# flatsat-breakout-main.net
KiCad netlist of a schematic drawn in EAGLE
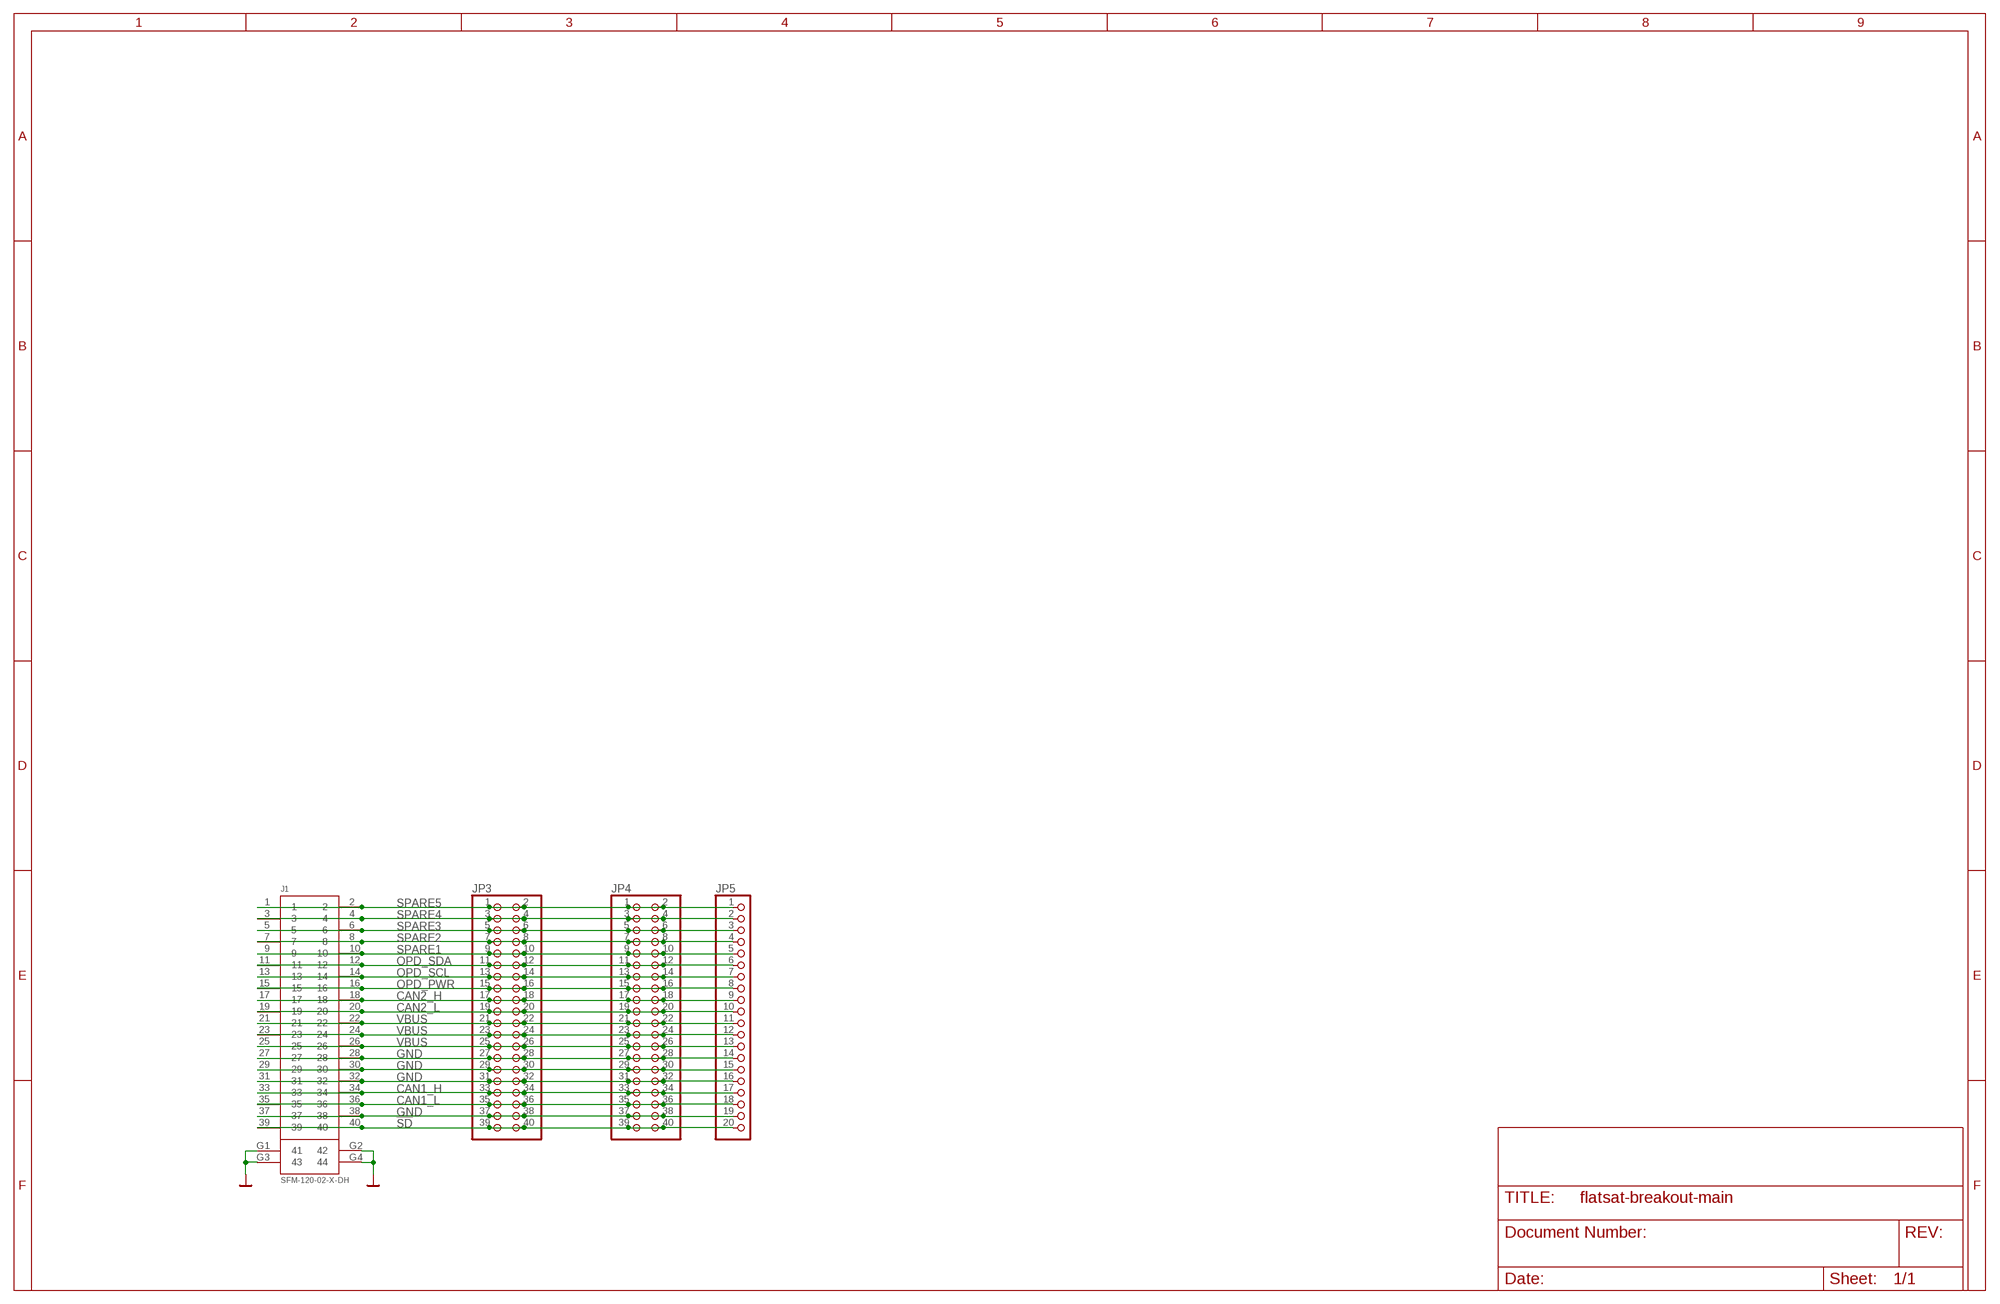
[diagram p0: schematic, sheet 1]

(export (version "E")
  (design (tool "Eeschema 10.0.6"))
  (components
    (comp (ref "J1")
      (value "SFM-120-02-X-DH")
      (footprint "eagle-import:SFM-120-02-X-DH")
      (libsource (lib "eagle-import") (part "SFM-120-02-X-DH"))
    )
    (comp (ref "JP3")
      (value "PINHD-2X20")
      (footprint "eagle-import:2X20")
      (libsource (lib "eagle-import") (part "PINHD-2X20"))
    )
    (comp (ref "JP4")
      (value "PINHD-2X20")
      (footprint "eagle-import:2X20")
      (libsource (lib "eagle-import") (part "PINHD-2X20"))
    )
    (comp (ref "JP5")
      (value "PINHD-1X20")
      (footprint "eagle-import:1X20")
      (libsource (lib "eagle-import") (part "PINHD-1X20"))
    )
  )
  (nets
    (net (code "1") (name "/CAN1_H") (class "Default")
      (node (ref "J1") (pin "33") (pinfunction "33_33") (pintype "bidirectional"))
      (node (ref "J1") (pin "34") (pinfunction "34_34") (pintype "bidirectional"))
      (node (ref "JP3") (pin "33") (pinfunction "33_33") (pintype "passive"))
      (node (ref "JP3") (pin "34") (pinfunction "34_34") (pintype "passive"))
      (node (ref "JP4") (pin "33") (pinfunction "33_33") (pintype "passive"))
      (node (ref "JP4") (pin "34") (pinfunction "34_34") (pintype "passive"))
      (node (ref "JP5") (pin "17") (pinfunction "17_17") (pintype "passive"))
    )
    (net (code "2") (name "/CAN1_L") (class "Default")
      (node (ref "J1") (pin "35") (pinfunction "35_35") (pintype "bidirectional"))
      (node (ref "J1") (pin "36") (pinfunction "36_36") (pintype "bidirectional"))
      (node (ref "JP3") (pin "35") (pinfunction "35_35") (pintype "passive"))
      (node (ref "JP3") (pin "36") (pinfunction "36_36") (pintype "passive"))
      (node (ref "JP4") (pin "35") (pinfunction "35_35") (pintype "passive"))
      (node (ref "JP4") (pin "36") (pinfunction "36_36") (pintype "passive"))
      (node (ref "JP5") (pin "18") (pinfunction "18_18") (pintype "passive"))
    )
    (net (code "3") (name "/CAN2_H") (class "Default")
      (node (ref "J1") (pin "17") (pinfunction "17_17") (pintype "bidirectional"))
      (node (ref "J1") (pin "18") (pinfunction "18_18") (pintype "bidirectional"))
      (node (ref "JP3") (pin "17") (pinfunction "17_17") (pintype "passive"))
      (node (ref "JP3") (pin "18") (pinfunction "18_18") (pintype "passive"))
      (node (ref "JP4") (pin "17") (pinfunction "17_17") (pintype "passive"))
      (node (ref "JP4") (pin "18") (pinfunction "18_18") (pintype "passive"))
      (node (ref "JP5") (pin "9") (pinfunction "9_9") (pintype "passive"))
    )
    (net (code "4") (name "/CAN2_L") (class "Default")
      (node (ref "J1") (pin "19") (pinfunction "19_19") (pintype "bidirectional"))
      (node (ref "J1") (pin "20") (pinfunction "20_20") (pintype "bidirectional"))
      (node (ref "JP3") (pin "19") (pinfunction "19_19") (pintype "passive"))
      (node (ref "JP3") (pin "20") (pinfunction "20_20") (pintype "passive"))
      (node (ref "JP4") (pin "19") (pinfunction "19_19") (pintype "passive"))
      (node (ref "JP4") (pin "20") (pinfunction "20_20") (pintype "passive"))
      (node (ref "JP5") (pin "10") (pinfunction "10_10") (pintype "passive"))
    )
    (net (code "5") (name "/OPD_PWR") (class "Default")
      (node (ref "J1") (pin "15") (pinfunction "15_15") (pintype "bidirectional"))
      (node (ref "J1") (pin "16") (pinfunction "16_16") (pintype "bidirectional"))
      (node (ref "JP3") (pin "15") (pinfunction "15_15") (pintype "passive"))
      (node (ref "JP3") (pin "16") (pinfunction "16_16") (pintype "passive"))
      (node (ref "JP4") (pin "15") (pinfunction "15_15") (pintype "passive"))
      (node (ref "JP4") (pin "16") (pinfunction "16_16") (pintype "passive"))
      (node (ref "JP5") (pin "8") (pinfunction "8_8") (pintype "passive"))
    )
    (net (code "6") (name "/OPD_SCL") (class "Default")
      (node (ref "J1") (pin "13") (pinfunction "13_13") (pintype "bidirectional"))
      (node (ref "J1") (pin "14") (pinfunction "14_14") (pintype "bidirectional"))
      (node (ref "JP3") (pin "13") (pinfunction "13_13") (pintype "passive"))
      (node (ref "JP3") (pin "14") (pinfunction "14_14") (pintype "passive"))
      (node (ref "JP4") (pin "13") (pinfunction "13_13") (pintype "passive"))
      (node (ref "JP4") (pin "14") (pinfunction "14_14") (pintype "passive"))
      (node (ref "JP5") (pin "7") (pinfunction "7_7") (pintype "passive"))
    )
    (net (code "7") (name "/OPD_SDA") (class "Default")
      (node (ref "J1") (pin "11") (pinfunction "11_11") (pintype "bidirectional"))
      (node (ref "J1") (pin "12") (pinfunction "12_12") (pintype "bidirectional"))
      (node (ref "JP3") (pin "11") (pinfunction "11_11") (pintype "passive"))
      (node (ref "JP3") (pin "12") (pinfunction "12_12") (pintype "passive"))
      (node (ref "JP4") (pin "11") (pinfunction "11_11") (pintype "passive"))
      (node (ref "JP4") (pin "12") (pinfunction "12_12") (pintype "passive"))
      (node (ref "JP5") (pin "6") (pinfunction "6_6") (pintype "passive"))
    )
    (net (code "8") (name "/SPARE1") (class "Default")
      (node (ref "J1") (pin "10") (pinfunction "10_10") (pintype "bidirectional"))
      (node (ref "J1") (pin "9") (pinfunction "9_9") (pintype "bidirectional"))
      (node (ref "JP3") (pin "10") (pinfunction "10_10") (pintype "passive"))
      (node (ref "JP3") (pin "9") (pinfunction "9_9") (pintype "passive"))
      (node (ref "JP4") (pin "10") (pinfunction "10_10") (pintype "passive"))
      (node (ref "JP4") (pin "9") (pinfunction "9_9") (pintype "passive"))
      (node (ref "JP5") (pin "5") (pinfunction "5_5") (pintype "passive"))
    )
    (net (code "9") (name "/SPARE2") (class "Default")
      (node (ref "J1") (pin "7") (pinfunction "7_7") (pintype "bidirectional"))
      (node (ref "J1") (pin "8") (pinfunction "8_8") (pintype "bidirectional"))
      (node (ref "JP3") (pin "7") (pinfunction "7_7") (pintype "passive"))
      (node (ref "JP3") (pin "8") (pinfunction "8_8") (pintype "passive"))
      (node (ref "JP4") (pin "7") (pinfunction "7_7") (pintype "passive"))
      (node (ref "JP4") (pin "8") (pinfunction "8_8") (pintype "passive"))
      (node (ref "JP5") (pin "4") (pinfunction "4_4") (pintype "passive"))
    )
    (net (code "10") (name "/SPARE3") (class "Default")
      (node (ref "J1") (pin "5") (pinfunction "5_5") (pintype "bidirectional"))
      (node (ref "J1") (pin "6") (pinfunction "6_6") (pintype "bidirectional"))
      (node (ref "JP3") (pin "5") (pinfunction "5_5") (pintype "passive"))
      (node (ref "JP3") (pin "6") (pinfunction "6_6") (pintype "passive"))
      (node (ref "JP4") (pin "5") (pinfunction "5_5") (pintype "passive"))
      (node (ref "JP4") (pin "6") (pinfunction "6_6") (pintype "passive"))
      (node (ref "JP5") (pin "3") (pinfunction "3_3") (pintype "passive"))
    )
    (net (code "11") (name "/SPARE4") (class "Default")
      (node (ref "J1") (pin "3") (pinfunction "3_3") (pintype "bidirectional"))
      (node (ref "J1") (pin "4") (pinfunction "4_4") (pintype "bidirectional"))
      (node (ref "JP3") (pin "3") (pinfunction "3_3") (pintype "passive"))
      (node (ref "JP3") (pin "4") (pinfunction "4_4") (pintype "passive"))
      (node (ref "JP4") (pin "3") (pinfunction "3_3") (pintype "passive"))
      (node (ref "JP4") (pin "4") (pinfunction "4_4") (pintype "passive"))
      (node (ref "JP5") (pin "2") (pinfunction "2_2") (pintype "passive"))
    )
    (net (code "12") (name "/SPARE5") (class "Default")
      (node (ref "J1") (pin "1") (pinfunction "1_1") (pintype "bidirectional"))
      (node (ref "J1") (pin "2") (pinfunction "2_2") (pintype "bidirectional"))
      (node (ref "JP3") (pin "1") (pinfunction "1_1") (pintype "passive"))
      (node (ref "JP3") (pin "2") (pinfunction "2_2") (pintype "passive"))
      (node (ref "JP4") (pin "1") (pinfunction "1_1") (pintype "passive"))
      (node (ref "JP4") (pin "2") (pinfunction "2_2") (pintype "passive"))
      (node (ref "JP5") (pin "1") (pinfunction "1_1") (pintype "passive"))
    )
    (net (code "13") (name "/VBUS") (class "Default")
      (node (ref "J1") (pin "21") (pinfunction "21_21") (pintype "bidirectional"))
      (node (ref "J1") (pin "22") (pinfunction "22_22") (pintype "bidirectional"))
      (node (ref "J1") (pin "23") (pinfunction "23_23") (pintype "bidirectional"))
      (node (ref "J1") (pin "24") (pinfunction "24_24") (pintype "bidirectional"))
      (node (ref "J1") (pin "25") (pinfunction "25_25") (pintype "bidirectional"))
      (node (ref "J1") (pin "26") (pinfunction "26_26") (pintype "bidirectional"))
      (node (ref "JP3") (pin "21") (pinfunction "21_21") (pintype "passive"))
      (node (ref "JP3") (pin "22") (pinfunction "22_22") (pintype "passive"))
      (node (ref "JP3") (pin "23") (pinfunction "23_23") (pintype "passive"))
      (node (ref "JP3") (pin "24") (pinfunction "24_24") (pintype "passive"))
      (node (ref "JP3") (pin "25") (pinfunction "25_25") (pintype "passive"))
      (node (ref "JP3") (pin "26") (pinfunction "26_26") (pintype "passive"))
      (node (ref "JP4") (pin "21") (pinfunction "21_21") (pintype "passive"))
      (node (ref "JP4") (pin "22") (pinfunction "22_22") (pintype "passive"))
      (node (ref "JP4") (pin "23") (pinfunction "23_23") (pintype "passive"))
      (node (ref "JP4") (pin "24") (pinfunction "24_24") (pintype "passive"))
      (node (ref "JP4") (pin "25") (pinfunction "25_25") (pintype "passive"))
      (node (ref "JP4") (pin "26") (pinfunction "26_26") (pintype "passive"))
      (node (ref "JP5") (pin "11") (pinfunction "11_11") (pintype "passive"))
      (node (ref "JP5") (pin "12") (pinfunction "12_12") (pintype "passive"))
      (node (ref "JP5") (pin "13") (pinfunction "13_13") (pintype "passive"))
    )
    (net (code "14") (name "/~{SD}") (class "Default")
      (node (ref "J1") (pin "39") (pinfunction "39_39") (pintype "bidirectional"))
      (node (ref "J1") (pin "40") (pinfunction "40_40") (pintype "bidirectional"))
      (node (ref "JP3") (pin "39") (pinfunction "39_39") (pintype "passive"))
      (node (ref "JP3") (pin "40") (pinfunction "40_40") (pintype "passive"))
      (node (ref "JP4") (pin "39") (pinfunction "39_39") (pintype "passive"))
      (node (ref "JP4") (pin "40") (pinfunction "40_40") (pintype "passive"))
      (node (ref "JP5") (pin "20") (pinfunction "20_20") (pintype "passive"))
    )
    (net (code "15") (name "GND") (class "Default")
      (node (ref "J1") (pin "27") (pinfunction "27_27") (pintype "bidirectional"))
      (node (ref "J1") (pin "28") (pinfunction "28_28") (pintype "bidirectional"))
      (node (ref "J1") (pin "29") (pinfunction "29_29") (pintype "bidirectional"))
      (node (ref "J1") (pin "30") (pinfunction "30_30") (pintype "bidirectional"))
      (node (ref "J1") (pin "31") (pinfunction "31_31") (pintype "bidirectional"))
      (node (ref "J1") (pin "32") (pinfunction "32_32") (pintype "bidirectional"))
      (node (ref "J1") (pin "37") (pinfunction "37_37") (pintype "bidirectional"))
      (node (ref "J1") (pin "38") (pinfunction "38_38") (pintype "bidirectional"))
      (node (ref "J1") (pin "G1") (pinfunction "41_G1") (pintype "bidirectional"))
      (node (ref "J1") (pin "G2") (pinfunction "42_G2") (pintype "bidirectional"))
      (node (ref "J1") (pin "G3") (pinfunction "43_G3") (pintype "bidirectional"))
      (node (ref "J1") (pin "G4") (pinfunction "44_G4") (pintype "bidirectional"))
      (node (ref "JP3") (pin "27") (pinfunction "27_27") (pintype "passive"))
      (node (ref "JP3") (pin "28") (pinfunction "28_28") (pintype "passive"))
      (node (ref "JP3") (pin "29") (pinfunction "29_29") (pintype "passive"))
      (node (ref "JP3") (pin "30") (pinfunction "30_30") (pintype "passive"))
      (node (ref "JP3") (pin "31") (pinfunction "31_31") (pintype "passive"))
      (node (ref "JP3") (pin "32") (pinfunction "32_32") (pintype "passive"))
      (node (ref "JP3") (pin "37") (pinfunction "37_37") (pintype "passive"))
      (node (ref "JP3") (pin "38") (pinfunction "38_38") (pintype "passive"))
      (node (ref "JP4") (pin "27") (pinfunction "27_27") (pintype "passive"))
      (node (ref "JP4") (pin "28") (pinfunction "28_28") (pintype "passive"))
      (node (ref "JP4") (pin "29") (pinfunction "29_29") (pintype "passive"))
      (node (ref "JP4") (pin "30") (pinfunction "30_30") (pintype "passive"))
      (node (ref "JP4") (pin "31") (pinfunction "31_31") (pintype "passive"))
      (node (ref "JP4") (pin "32") (pinfunction "32_32") (pintype "passive"))
      (node (ref "JP4") (pin "37") (pinfunction "37_37") (pintype "passive"))
      (node (ref "JP4") (pin "38") (pinfunction "38_38") (pintype "passive"))
      (node (ref "JP5") (pin "14") (pinfunction "14_14") (pintype "passive"))
      (node (ref "JP5") (pin "15") (pinfunction "15_15") (pintype "passive"))
      (node (ref "JP5") (pin "16") (pinfunction "16_16") (pintype "passive"))
      (node (ref "JP5") (pin "19") (pinfunction "19_19") (pintype "passive"))
    )
  )
)
